# LC_LPF2.net
KiCad netlist of a schematic drawn in Altium Designer
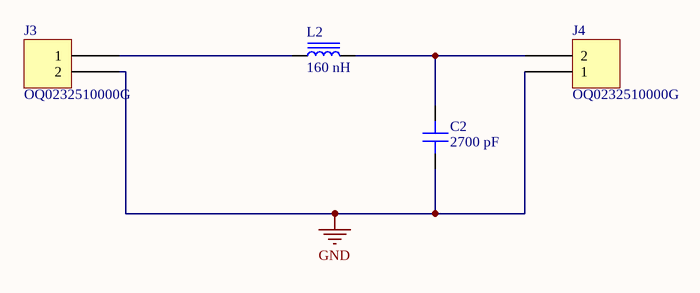
[diagram p0: LC_LPF2.SchDoc]

(export (version "E")
  (design (tool "Eeschema 10.0.6"))
  (components
    (comp (ref "C2")
      (value "2700 pF")
      (footprint "CAP 0603_1608")
      (description "CAP CER 2700PF 25V NP0 0603")
      (fields (field (name "PART NUMBER") "C0603C272F3GAC7867") (field (name "MANUFACTURER") "KEMET"))
      (libsource (lib "Celestial Altium Library - altium_library") (part "Capacitor"))
    )
    (comp (ref "J3")
      (value "OQ0232510000G")
      (footprint "FCI 06-381-2PIN")
      (description "TERM BLOCK HDR 2POS 90DEG 3.81MM")
      (fields (field (name "MANUFACTURER") "Amphenol Anytek"))
      (libsource (lib "Celestial Altium Library - altium_library") (part "2 Pin"))
    )
    (comp (ref "J4")
      (value "OQ0232510000G")
      (footprint "FCI 06-381-2PIN")
      (description "TERM BLOCK HDR 2POS 90DEG 3.81MM")
      (fields (field (name "MANUFACTURER") "Amphenol Anytek"))
      (libsource (lib "") (part "2 Pin_1"))
    )
    (comp (ref "L2")
      (value "160 nH")
      (footprint "IND 0402_1005 RF WW")
      (description "FIXED IND 160NH 480MA 330MOHM SM")
      (fields
        (field (name "PART NUMBER") "LQW15CNR16J00D")
        (field (name "MANUFACTURER") "Murata Electronics")
      )
      (libsource (lib "Celestial Altium Library - altium_library") (part "Inductor"))
    )
  )
  (nets
    (net (code "1") (name "GND") (class "Default")
      (node (ref "C2") (pin "1") (pinfunction "1_1") (pintype "passive"))
      (node (ref "J3") (pin "2") (pinfunction "2_2") (pintype "passive"))
      (node (ref "J4") (pin "1") (pinfunction "1_1") (pintype "passive"))
    )
    (net (code "2") (name "Net-(C2-Pad2)") (class "Default")
      (node (ref "C2") (pin "2") (pinfunction "2_2") (pintype "passive"))
      (node (ref "J4") (pin "2") (pinfunction "2_2") (pintype "passive"))
      (node (ref "L2") (pin "2") (pinfunction "2_2") (pintype "passive"))
    )
    (net (code "3") (name "Net-(J3-Pad1)") (class "Default")
      (node (ref "J3") (pin "1") (pinfunction "1_1") (pintype "passive"))
      (node (ref "L2") (pin "1") (pinfunction "1_1") (pintype "passive"))
    )
  )
)
